# 12V_9V_Power_Stage.net
KiCad netlist of a schematic drawn in Altium Designer
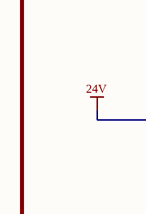
[diagram p0: 12V_9V_Power_Stage.SchDoc, left]
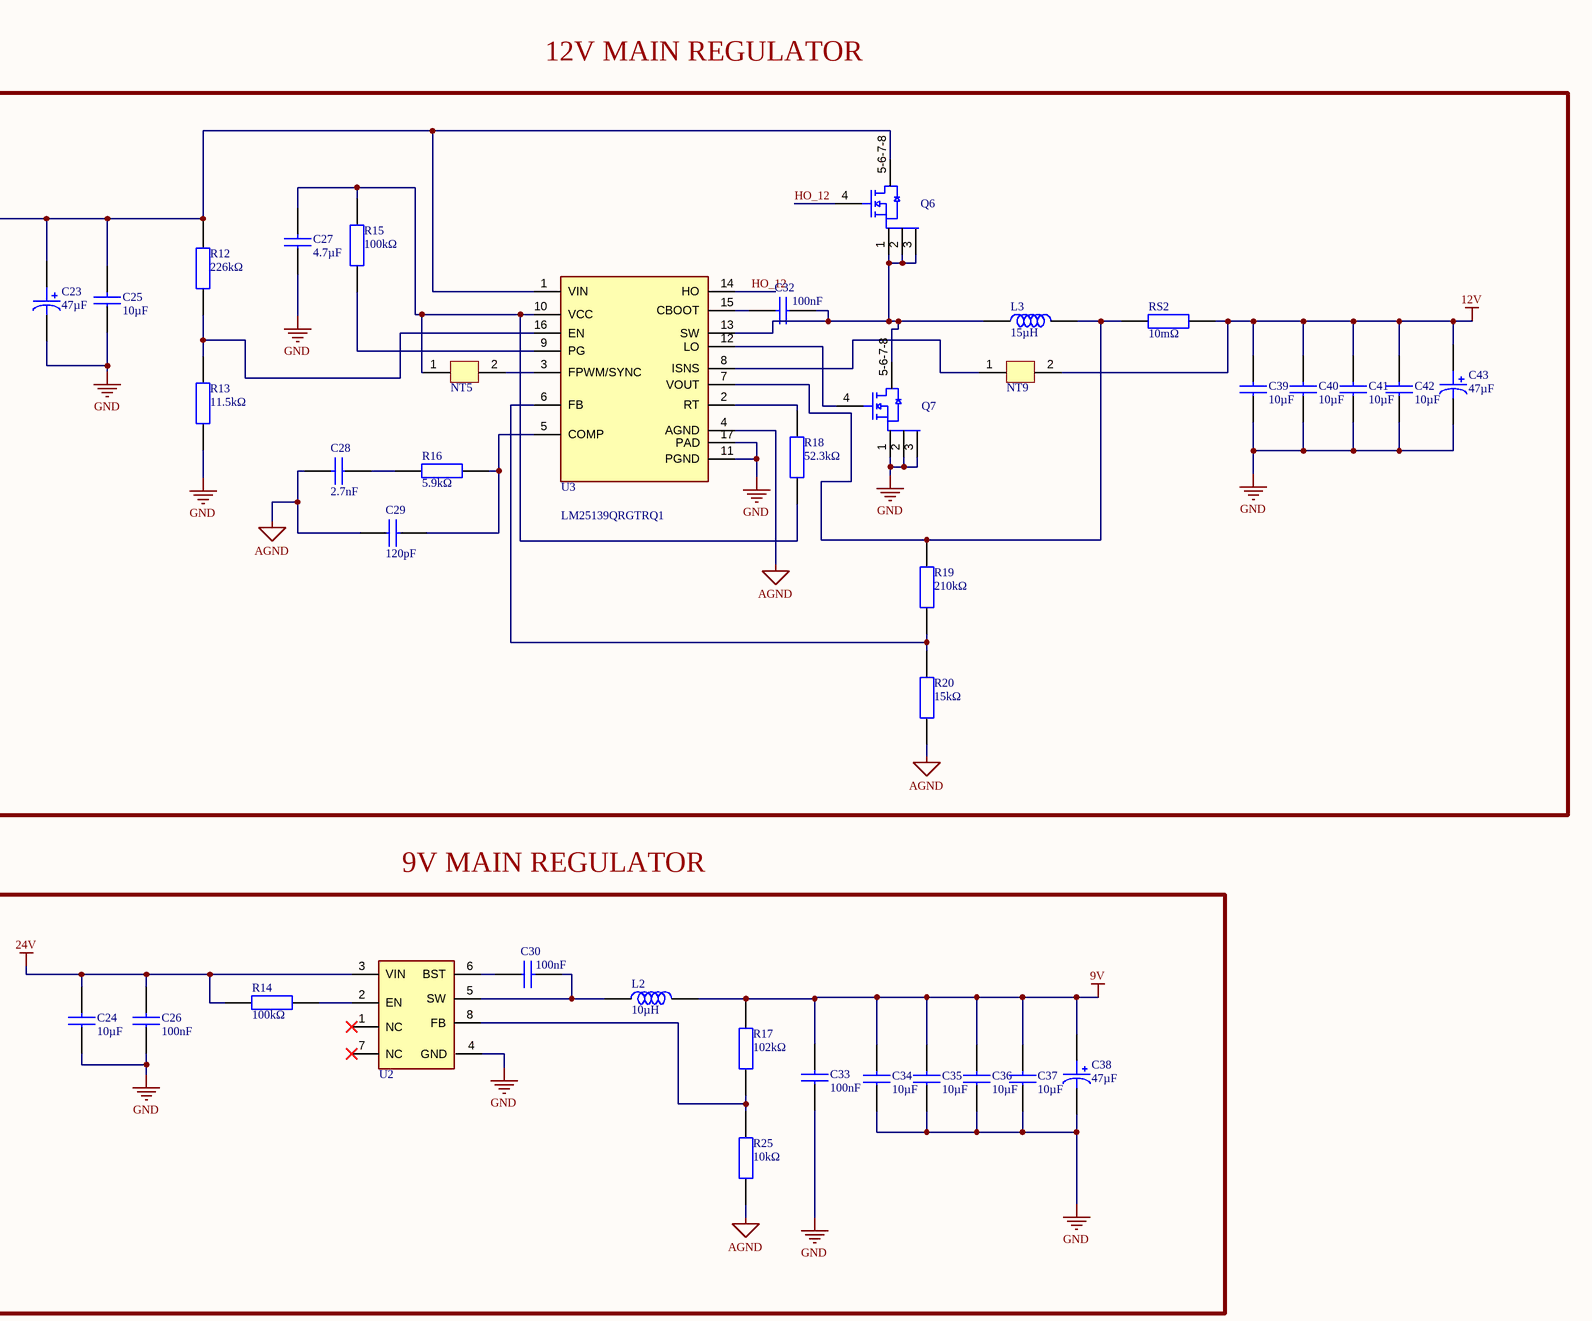
[diagram p1: 12V_9V_Power_Stage.SchDoc, right]

(export (version "E")
  (design (tool "Eeschema 10.0.6"))
  (components
    (comp (ref "C23")
      (value "47µF")
      (footprint "CAP ALUM SMD")
      (description "Conductive Polymer Hybrid Aluminum Electrolytic Capacitors, 47µF, 50V, -55 to 105¡C")
      (fields
        (field (name "MANUFACTURER") "Panasonic")
        (field (name "MANUFACTURER PART NUMBER") "EEH-ZA1H470P")
      )
      (libsource (lib "PDU_BOM") (part "EEHZA1H470P"))
    )
    (comp (ref "C24")
      (value "10µF")
      (footprint "CAP_1210_S")
      (description "50V 10uF X5R 卤10% 1210 Multilayer Ceramic Capacitors MLCC - SMD/SMT ROHS")
      (fields
        (field (name "MANUFACTURER") "Samsung Electro-Mechanics")
        (field (name "MANUFACTURER PART NUMBER") "CL32A106KBJNNNE")
      )
      (libsource (lib "PDU_BOM") (part "CL32A106KBJNNNE"))
    )
    (comp (ref "C25")
      (value "10µF")
      (footprint "CAP_1206")
      (description "50V 10uF X7R 卤10% 1206 Multilayer Ceramic Capacitors MLCC - SMD/SMT ROHS")
      (fields
        (field (name "MANUFACTURER") "TDK")
        (field (name "MANUFACTURER PART NUMBER") "C3216X7R1H106K160AC")
      )
      (libsource (lib "PDU_BOM") (part "C3216X7R1H106K160AC"))
    )
    (comp (ref "C26")
      (value "100nF")
      (footprint "CAP_0603")
      (description "CGA Series 0603 100 nF 50 V ±10 % Tolerance X7R SMT Multilayer Ceramic Capacitor")
      (fields
        (field (name "MANUFACTURER") "TDK")
        (field (name "MANUFACTURER PART NUMBER") "CGA3E2X7R1H104K080AA")
      )
      (libsource (lib "PDU_BOM") (part "CGA3E2X7R1H104K080AA"))
    )
    (comp (ref "C27")
      (value "4.7µF")
      (footprint "CAP_0805")
      (description "10V 4.7uF X7R ±10% 0805 Multilayer Ceramic Capacitors MLCC - SMD/SMT ROHS")
      (fields
        (field (name "MANUFACTURER") "TAIYO YUDEN")
        (field (name "MANUFACTURER PART NUMBER") "LMK212B7475KG-T")
      )
      (libsource (lib "PDU_BOM") (part "LMK212B7475KG-T"))
    )
    (comp (ref "C28")
      (value "2.7nF")
      (footprint "CAP_0603")
      (description "0603 2.7 nF 50 V ±5% Tolerance C0G SMT Multilayer Ceramic Capacitor")
      (fields
        (field (name "MANUFACTURER") "Murata")
        (field (name "MANUFACTURER PART NUMBER") "GRM1885C1H272JA01J")
      )
      (libsource (lib "PDU_BOM") (part "GRM1885C1H272JA01J"))
    )
    (comp (ref "C29")
      (value "120pF")
      (footprint "CAP_0402")
      (description "Multilayer Ceramic Capacitors 120pF 50V C0G 5% SMD 0402")
      (fields
        (field (name "MANUFACTURER") "TAIYO YUDEN")
        (field (name "MANUFACTURER PART NUMBER") "UMK105CG121JV-F")
      )
      (libsource (lib "PDU_BOM") (part "UMK105CG121JV-F"))
    )
    (comp (ref "C30")
      (value "100nF")
      (footprint "CAP_0402")
      (description "C Series 0201 0.1 uF 10 V ±10 % Tolerance X5R SMT Multilayer Ceramic Capacitor")
      (fields
        (field (name "MANUFACTURER") "TDK")
        (field (name "MANUFACTURER PART NUMBER") "C0603X5R1A104K030BC")
      )
      (libsource (lib "PDU_BOM") (part "C0603X5R1A104K030BC"))
    )
    (comp (ref "C32")
      (value "100nF")
      (footprint "CAP_0402")
      (description "10V 100nF X7R ±10% 0402 Multilayer Ceramic Capacitors MLCC - SMD/SMT ROHS")
      (fields
        (field (name "MANUFACTURER") "Murata")
        (field (name "MANUFACTURER PART NUMBER") "GRM155R71A104KA01D")
      )
      (libsource (lib "PDU_BOM") (part "GRM155R71A104KA01D"))
    )
    (comp (ref "C33")
      (value "100nF")
      (footprint "CAP_0603")
      (description "CGA Series 0603 100 nF 50 V ±10 % Tolerance X7R SMT Multilayer Ceramic Capacitor")
      (fields
        (field (name "MANUFACTURER") "TDK")
        (field (name "MANUFACTURER PART NUMBER") "CGA3E2X7R1H104K080AA")
      )
      (libsource (lib "PDU_BOM") (part "CGA3E2X7R1H104K080AA"))
    )
    (comp (ref "C34")
      (value "10µF")
      (footprint "CAP_1206")
      (description "25V 10uF X7R ±10% 1206 Multilayer Ceramic Capacitors MLCC - SMD/SMT ROHS")
      (fields
        (field (name "MANUFACTURER") "Murata")
        (field (name "MANUFACTURER PART NUMBER") "GRM31CR71E106KA12L")
      )
      (libsource (lib "PDU_BOM") (part "GRM31CR71E106KA12L"))
    )
    (comp (ref "C35")
      (value "10µF")
      (footprint "CAP_1206")
      (description "25V 10uF X7R ±10% 1206 Multilayer Ceramic Capacitors MLCC - SMD/SMT ROHS")
      (fields
        (field (name "MANUFACTURER") "Murata")
        (field (name "MANUFACTURER PART NUMBER") "GRM31CR71E106KA12L")
      )
      (libsource (lib "PDU_BOM") (part "GRM31CR71E106KA12L"))
    )
    (comp (ref "C36")
      (value "10µF")
      (footprint "CAP_1206")
      (description "25V 10uF X7R ±10% 1206 Multilayer Ceramic Capacitors MLCC - SMD/SMT ROHS")
      (fields
        (field (name "MANUFACTURER") "Murata")
        (field (name "MANUFACTURER PART NUMBER") "GRM31CR71E106KA12L")
      )
      (libsource (lib "PDU_BOM") (part "GRM31CR71E106KA12L"))
    )
    (comp (ref "C37")
      (value "10µF")
      (footprint "CAP_1206")
      (description "25V 10uF X7R ±10% 1206 Multilayer Ceramic Capacitors MLCC - SMD/SMT ROHS")
      (fields
        (field (name "MANUFACTURER") "Murata")
        (field (name "MANUFACTURER PART NUMBER") "GRM31CR71E106KA12L")
      )
      (libsource (lib "PDU_BOM") (part "GRM31CR71E106KA12L"))
    )
    (comp (ref "C38")
      (value "47µF")
      (footprint "CAP ALUM SMD")
      (description "Conductive Polymer Hybrid Aluminum Electrolytic Capacitors, 47µF, 50V, -55 to 105¡C")
      (fields
        (field (name "MANUFACTURER") "Panasonic")
        (field (name "MANUFACTURER PART NUMBER") "EEH-ZA1H470P")
      )
      (libsource (lib "PDU_BOM") (part "EEHZA1H470P"))
    )
    (comp (ref "C39")
      (value "10µF")
      (footprint "CAP_1206")
      (description "25V 10uF X7R ±10% 1206 Multilayer Ceramic Capacitors MLCC - SMD/SMT ROHS")
      (fields
        (field (name "MANUFACTURER") "Murata")
        (field (name "MANUFACTURER PART NUMBER") "GRM31CR71E106KA12L")
      )
      (libsource (lib "PDU_BOM") (part "GRM31CR71E106KA12L"))
    )
    (comp (ref "C40")
      (value "10µF")
      (footprint "CAP_1206")
      (description "25V 10uF X7R ±10% 1206 Multilayer Ceramic Capacitors MLCC - SMD/SMT ROHS")
      (fields
        (field (name "MANUFACTURER") "Murata")
        (field (name "MANUFACTURER PART NUMBER") "GRM31CR71E106KA12L")
      )
      (libsource (lib "PDU_BOM") (part "GRM31CR71E106KA12L"))
    )
    (comp (ref "C41")
      (value "10µF")
      (footprint "CAP_1206")
      (description "25V 10uF X7R ±10% 1206 Multilayer Ceramic Capacitors MLCC - SMD/SMT ROHS")
      (fields
        (field (name "MANUFACTURER") "Murata")
        (field (name "MANUFACTURER PART NUMBER") "GRM31CR71E106KA12L")
      )
      (libsource (lib "PDU_BOM") (part "GRM31CR71E106KA12L"))
    )
    (comp (ref "C42")
      (value "10µF")
      (footprint "CAP_1206")
      (description "25V 10uF X7R ±10% 1206 Multilayer Ceramic Capacitors MLCC - SMD/SMT ROHS")
      (fields
        (field (name "MANUFACTURER") "Murata")
        (field (name "MANUFACTURER PART NUMBER") "GRM31CR71E106KA12L")
      )
      (libsource (lib "PDU_BOM") (part "GRM31CR71E106KA12L"))
    )
    (comp (ref "C43")
      (value "47µF")
      (footprint "CAP ALUM SMD")
      (description "Conductive Polymer Hybrid Aluminum Electrolytic Capacitors, 47µF, 50V, -55 to 105¡C")
      (fields
        (field (name "MANUFACTURER") "Panasonic")
        (field (name "MANUFACTURER PART NUMBER") "EEH-ZA1H470P")
      )
      (libsource (lib "PDU_BOM") (part "EEHZA1H470P"))
    )
    (comp (ref "L2")
      (value "10µH")
      (footprint "SRR1208")
      (description "Inductor Power Shielded Wirewound 10uH 20% 1KHz 20Q-Factor Ferrite 5A 0.021Ohm DCR T/R")
      (fields
        (field (name "MANUFACTURER") "Bourns")
        (field (name "MANUFACTURER PART NUMBER") "SRR1208-100ML")
      )
      (libsource (lib "PDU_BOM") (part "SRR1208-100ML"))
    )
    (comp (ref "L3")
      (value "15µH")
      (footprint "MSS1210")
      (description "General Purpose Inductor, 15uH, 20%, 1 Element, Ferrite-Core, SMD, 4848, CHIP, 4747")
      (fields
        (field (name "MANUFACTURER") "Coilcraft")
        (field (name "MANUFACTURER PART NUMBER") "MSS1210-153MED")
      )
      (libsource (lib "PDU_BOM") (part "MSS1210-153MED"))
    )
    (comp (ref "NT5") (value "Net-Tie") (footprint "Net-Tie") (libsource (lib "PDU_BOM") (part "Net-Tie")))
    (comp (ref "NT9") (value "Net-Tie") (footprint "Net-Tie") (libsource (lib "PDU_BOM") (part "Net-Tie")))
    (comp (ref "Q6")
      (value "CSD18540Q5B")
      (footprint "SON 5X6")
      (description "60-V, N channel NexFET™ power MOSFET, single SON 5 mm x 6 mm, 2.2 mOhm 8-VSON-CLIP -55 to 175")
      (fields (field (name "MANUFACTURER") "Texas Instruments"))
      (libsource (lib "PDU_BOM") (part "CSD18540Q5B"))
    )
    (comp (ref "Q7")
      (value "CSD18540Q5B")
      (footprint "SON 5X6")
      (description "60-V, N channel NexFET™ power MOSFET, single SON 5 mm x 6 mm, 2.2 mOhm 8-VSON-CLIP -55 to 175")
      (fields (field (name "MANUFACTURER") "Texas Instruments"))
      (libsource (lib "PDU_BOM") (part "CSD18540Q5B"))
    )
    (comp (ref "R12")
      (value "226kΩ")
      (footprint "RES_0402")
      (description "Fixed Resistor, Metal Glaze/Thick Film, 0.063W, 226000ohm, 50V, 1% +/-Tol, Surface Mount, 0402")
      (fields
        (field (name "MANUFACTURER") "Vishay")
        (field (name "MANUFACTURER PART NUMBER") "CRCW0402226KFKED")
      )
      (libsource (lib "PDU_BOM") (part "CRCW0402226KFKED"))
    )
    (comp (ref "R13")
      (value "11.5kΩ")
      (footprint "RES_0402")
      (description "Res Thick Film 0402 11.5K Ohm 1% 1/16W ±100ppm/°C Molded SMD SMD Paper T/R")
      (fields
        (field (name "MANUFACTURER") "Vishay")
        (field (name "MANUFACTURER PART NUMBER") "CRCW040211K5FKED")
      )
      (libsource (lib "PDU_BOM") (part "CRCW040211K5FKED"))
    )
    (comp (ref "R14")
      (value "100kΩ")
      (footprint "RES_0603")
      (description "Res Thick Film 0603 100K Ohm 1% 1/3W ±100ppm/°C Molded SMD SMD Paper T/R")
      (fields
        (field (name "MANUFACTURER") "Vishay")
        (field (name "MANUFACTURER PART NUMBER") "CRCW0603100KFKEAHP")
      )
      (libsource (lib "") (part "CRCW0603100KFKEA_1"))
    )
    (comp (ref "R15")
      (value "100kΩ")
      (footprint "RES_0603")
      (description "Res Thick Film 0603 100K Ohm 1% 1/3W ±100ppm/°C Molded SMD SMD Paper T/R")
      (fields
        (field (name "MANUFACTURER") "Vishay")
        (field (name "MANUFACTURER PART NUMBER") "CRCW0603100KFKEAHP")
      )
      (libsource (lib "PDU_BOM") (part "CRCW0603100KFKEA"))
    )
    (comp (ref "R16")
      (value "5.9kΩ")
      (footprint "RES_0402")
      (description "Res Thick Film 0402 5.9K Ohm 1% 1/16W ±100ppm/°C Molded SMD Paper T/R")
      (fields
        (field (name "MANUFACTURER") "Vishay")
        (field (name "MANUFACTURER PART NUMBER") "CRCW04025K90FKED")
      )
      (libsource (lib "PDU_BOM") (part "CRCW04025K90FKED"))
    )
    (comp (ref "R17")
      (value "102kΩ")
      (footprint "RES_0402")
      (description "63mW Thick Film Resistors 75V ±1% ±100ppm/℃ 102kΩ 0402 Chip Resistor - Surface Mount ROHS")
      (fields
        (field (name "MANUFACTURER") "Vishay")
        (field (name "MANUFACTURER PART NUMBER") "CRCW0402102KFKED")
      )
      (libsource (lib "PDU_BOM") (part "CRCW0402102KFKED"))
    )
    (comp (ref "R18")
      (value "52.3kΩ")
      (footprint "RES_0603")
      (description "100mW Thick Film Resistors 75V ±1% ±100ppm/℃ 52.3kΩ 0603 Chip Resistor - Surface Mount ROHS")
      (fields
        (field (name "MANUFACTURER") "Vishay")
        (field (name "MANUFACTURER PART NUMBER") "CRCW060352K3FKEA")
      )
      (libsource (lib "PDU_BOM") (part "CRCW060352K3FKEA"))
    )
    (comp (ref "R19")
      (value "210kΩ")
      (footprint "RES_0402")
      (description "62.5mW Thick Film Resistors 50V ±1% ±100ppm/℃ 210kΩ 0402 Chip Resistor - Surface Mount ROHS")
      (fields
        (field (name "MANUFACTURER") "Vishay")
        (field (name "MANUFACTURER PART NUMBER") "CRCW0402210KFKED")
      )
      (libsource (lib "PDU_BOM") (part "CRCW0402210KFKED"))
    )
    (comp (ref "R20")
      (value "15kΩ")
      (footprint "RES_0402")
      (description "Res Thick Film 0402 15K Ohm 1% 1/16W ±100ppm/°C Molded SMD Paper T/R")
      (fields
        (field (name "MANUFACTURER") "Vishay")
        (field (name "MANUFACTURER PART NUMBER") "CRCW040215K0FKED")
      )
      (libsource (lib "PDU_BOM") (part "CRCW040215K0FKED"))
    )
    (comp (ref "R25")
      (value "10kΩ")
      (footprint "RES_0402")
      (description "Res Thick Film 0402 10K Ohm 1% 0.2W ±100ppm/°C Molded SMD SMD Paper T/R")
      (fields
        (field (name "MANUFACTURER") "Vishay")
        (field (name "MANUFACTURER PART NUMBER") "CRCW040210K0FKEDHP")
      )
      (libsource (lib "PDU_BOM") (part "CRCW040210K0FKED"))
    )
    (comp (ref "RS2")
      (value "10mΩ")
      (footprint "CAP_1206")
      (description "Res Thick Film 1206 0.01 Ohm 1% 1/2W Molded SMD Paper T/R")
      (fields
        (field (name "MANUFACTURER") "Stackpole Electronics")
        (field (name "MANUFACTURER PART NUMBER") "CSR1206FK10L0")
      )
      (libsource (lib "PDU_BOM") (part "CSR1206FK10L0"))
    )
    (comp (ref "U2")
      (value "TPS563300DRLR")
      (footprint "SOT-583-8")
      (description "3.8-V to 28-V Input, 3-A synchronous buck converter in SOT-583 package 8-SOT-5X3 -40 to 150")
      (fields (field (name "MANUFACTURER") "Texas Instruments"))
      (libsource (lib "PDU_BOM") (part "TPS563300DRLR"))
    )
    (comp (ref "U3")
      (value "LM25139QRGTRQ1")
      (footprint "16-VFQFN")
      (fields (field (name "MANUFACTURER") "Texas Instruments"))
      (libsource (lib "PDU_BOM") (part "LM25139QRGTRQ1"))
    )
  )
  (nets
    (net (code "1") (name "/HO_12") (class "Default")
      (node (ref "Q6") (pin "4") (pinfunction "G_4") (pintype "passive"))
      (node (ref "U3") (pin "14") (pinfunction "HO_14") (pintype "passive"))
    )
    (net (code "2") (name "9V") (class "Default")
      (node (ref "C33") (pin "2") (pinfunction "2_2") (pintype "passive"))
      (node (ref "C34") (pin "2") (pinfunction "2_2") (pintype "passive"))
      (node (ref "C35") (pin "2") (pinfunction "2_2") (pintype "passive"))
      (node (ref "C36") (pin "2") (pinfunction "2_2") (pintype "passive"))
      (node (ref "C37") (pin "2") (pinfunction "2_2") (pintype "passive"))
      (node (ref "C38") (pin "1") (pinfunction "C_1") (pintype "passive"))
      (node (ref "L2") (pin "2") (pinfunction "2_2") (pintype "passive"))
      (node (ref "R17") (pin "2") (pinfunction "2_2") (pintype "passive"))
    )
    (net (code "3") (name "12V") (class "Default")
      (node (ref "C39") (pin "2") (pinfunction "2_2") (pintype "passive"))
      (node (ref "C40") (pin "2") (pinfunction "2_2") (pintype "passive"))
      (node (ref "C41") (pin "2") (pinfunction "2_2") (pintype "passive"))
      (node (ref "C42") (pin "2") (pinfunction "2_2") (pintype "passive"))
      (node (ref "C43") (pin "1") (pinfunction "C_1") (pintype "passive"))
      (node (ref "NT9") (pin "2") (pinfunction "2_2") (pintype "passive"))
      (node (ref "RS2") (pin "2") (pinfunction "2_2") (pintype "passive"))
    )
    (net (code "4") (name "24V") (class "Default")
      (node (ref "C23") (pin "1") (pinfunction "C_1") (pintype "passive"))
      (node (ref "C24") (pin "2") (pinfunction "2_2") (pintype "passive"))
      (node (ref "C25") (pin "2") (pinfunction "2_2") (pintype "passive"))
      (node (ref "C26") (pin "2") (pinfunction "2_2") (pintype "passive"))
      (node (ref "Q6") (pin "5-6-7-8") (pinfunction "D_5-6-7-8") (pintype "passive"))
      (node (ref "R12") (pin "2") (pinfunction "2_2") (pintype "passive"))
      (node (ref "R14") (pin "1") (pinfunction "1_1") (pintype "passive"))
      (node (ref "U2") (pin "3") (pinfunction "VIN_3") (pintype "passive"))
      (node (ref "U3") (pin "1") (pinfunction "VIN_1") (pintype "passive"))
    )
    (net (code "5") (name "AGND") (class "Default")
      (node (ref "C28") (pin "2") (pinfunction "2_2") (pintype "passive"))
      (node (ref "C29") (pin "1") (pinfunction "1_1") (pintype "passive"))
      (node (ref "R20") (pin "1") (pinfunction "1_1") (pintype "passive"))
      (node (ref "R25") (pin "1") (pinfunction "1_1") (pintype "passive"))
      (node (ref "U3") (pin "4") (pinfunction "AGND_4") (pintype "passive"))
    )
    (net (code "6") (name "GND") (class "Default")
      (node (ref "C23") (pin "2") (pinfunction "A_2") (pintype "passive"))
      (node (ref "C24") (pin "1") (pinfunction "1_1") (pintype "passive"))
      (node (ref "C25") (pin "1") (pinfunction "1_1") (pintype "passive"))
      (node (ref "C26") (pin "1") (pinfunction "1_1") (pintype "passive"))
      (node (ref "C27") (pin "1") (pinfunction "1_1") (pintype "passive"))
      (node (ref "C33") (pin "1") (pinfunction "1_1") (pintype "passive"))
      (node (ref "C34") (pin "1") (pinfunction "1_1") (pintype "passive"))
      (node (ref "C35") (pin "1") (pinfunction "1_1") (pintype "passive"))
      (node (ref "C36") (pin "1") (pinfunction "1_1") (pintype "passive"))
      (node (ref "C37") (pin "1") (pinfunction "1_1") (pintype "passive"))
      (node (ref "C38") (pin "2") (pinfunction "A_2") (pintype "passive"))
      (node (ref "C39") (pin "1") (pinfunction "1_1") (pintype "passive"))
      (node (ref "C40") (pin "1") (pinfunction "1_1") (pintype "passive"))
      (node (ref "C41") (pin "1") (pinfunction "1_1") (pintype "passive"))
      (node (ref "C42") (pin "1") (pinfunction "1_1") (pintype "passive"))
      (node (ref "C43") (pin "2") (pinfunction "A_2") (pintype "passive"))
      (node (ref "Q7") (pin "1") (pinfunction "S_1") (pintype "passive"))
      (node (ref "Q7") (pin "2") (pinfunction "S_2") (pintype "passive"))
      (node (ref "Q7") (pin "3") (pinfunction "S_3") (pintype "passive"))
      (node (ref "R13") (pin "1") (pinfunction "1_1") (pintype "passive"))
      (node (ref "U2") (pin "4") (pinfunction "GND_4") (pintype "passive"))
      (node (ref "U3") (pin "11") (pinfunction "PGND_11") (pintype "passive"))
      (node (ref "U3") (pin "17") (pinfunction "PAD_17") (pintype "passive"))
    )
    (net (code "7") (name "Net-(C28-Pad1)") (class "Default")
      (node (ref "C28") (pin "1") (pinfunction "1_1") (pintype "passive"))
      (node (ref "R16") (pin "1") (pinfunction "1_1") (pintype "passive"))
    )
    (net (code "8") (name "Net-(Q7-D)") (class "Default")
      (node (ref "C32") (pin "1") (pinfunction "1_1") (pintype "passive"))
      (node (ref "L3") (pin "1") (pinfunction "1_1") (pintype "passive"))
      (node (ref "Q6") (pin "1") (pinfunction "S_1") (pintype "passive"))
      (node (ref "Q6") (pin "2") (pinfunction "S_2") (pintype "passive"))
      (node (ref "Q6") (pin "3") (pinfunction "S_3") (pintype "passive"))
      (node (ref "Q7") (pin "5-6-7-8") (pinfunction "D_5-6-7-8") (pintype "passive"))
      (node (ref "U3") (pin "13") (pinfunction "SW_13") (pintype "passive"))
    )
    (net (code "9") (name "Net-(Q7-G)") (class "Default")
      (node (ref "Q7") (pin "4") (pinfunction "G_4") (pintype "passive"))
      (node (ref "U3") (pin "12") (pinfunction "LO_12") (pintype "passive"))
    )
    (net (code "10") (name "Net-(U2-BST)") (class "Default")
      (node (ref "C30") (pin "1") (pinfunction "1_1") (pintype "passive"))
      (node (ref "U2") (pin "6") (pinfunction "BST_6") (pintype "passive"))
    )
    (net (code "11") (name "Net-(U2-EN)") (class "Default")
      (node (ref "R14") (pin "2") (pinfunction "2_2") (pintype "passive"))
      (node (ref "U2") (pin "2") (pinfunction "EN_2") (pintype "passive"))
    )
    (net (code "12") (name "Net-(U2-FB)") (class "Default")
      (node (ref "R17") (pin "1") (pinfunction "1_1") (pintype "passive"))
      (node (ref "R25") (pin "2") (pinfunction "2_2") (pintype "passive"))
      (node (ref "U2") (pin "8") (pinfunction "FB_8") (pintype "passive"))
    )
    (net (code "13") (name "Net-(U2-SW)") (class "Default")
      (node (ref "C30") (pin "2") (pinfunction "2_2") (pintype "passive"))
      (node (ref "L2") (pin "1") (pinfunction "1_1") (pintype "passive"))
      (node (ref "U2") (pin "5") (pinfunction "SW_5") (pintype "passive"))
    )
    (net (code "14") (name "Net-(U3-CBOOT)") (class "Default")
      (node (ref "C32") (pin "2") (pinfunction "2_2") (pintype "passive"))
      (node (ref "U3") (pin "15") (pinfunction "CBOOT_15") (pintype "passive"))
    )
    (net (code "15") (name "Net-(U3-COMP)") (class "Default")
      (node (ref "C29") (pin "2") (pinfunction "2_2") (pintype "passive"))
      (node (ref "R16") (pin "2") (pinfunction "2_2") (pintype "passive"))
      (node (ref "U3") (pin "5") (pinfunction "COMP_5") (pintype "passive"))
    )
    (net (code "16") (name "Net-(U3-EN)") (class "Default")
      (node (ref "R12") (pin "1") (pinfunction "1_1") (pintype "passive"))
      (node (ref "R13") (pin "2") (pinfunction "2_2") (pintype "passive"))
      (node (ref "U3") (pin "16") (pinfunction "EN_16") (pintype "passive"))
    )
    (net (code "17") (name "Net-(U3-FB)") (class "Default")
      (node (ref "R19") (pin "1") (pinfunction "1_1") (pintype "passive"))
      (node (ref "R20") (pin "2") (pinfunction "2_2") (pintype "passive"))
      (node (ref "U3") (pin "6") (pinfunction "FB_6") (pintype "passive"))
    )
    (net (code "18") (name "Net-(U3-FPWM{slash}SYNC)") (class "Default")
      (node (ref "NT5") (pin "2") (pinfunction "2_2") (pintype "passive"))
      (node (ref "U3") (pin "3") (pinfunction "FPWM/SYNC_3") (pintype "passive"))
    )
    (net (code "19") (name "Net-(U3-ISNS)") (class "Default")
      (node (ref "NT9") (pin "1") (pinfunction "1_1") (pintype "passive"))
      (node (ref "U3") (pin "8") (pinfunction "ISNS_8") (pintype "passive"))
    )
    (net (code "20") (name "Net-(U3-PG)") (class "Default")
      (node (ref "R15") (pin "1") (pinfunction "1_1") (pintype "passive"))
      (node (ref "U3") (pin "9") (pinfunction "PG_9") (pintype "passive"))
    )
    (net (code "21") (name "Net-(U3-RT)") (class "Default")
      (node (ref "R18") (pin "2") (pinfunction "2_2") (pintype "passive"))
      (node (ref "U3") (pin "2") (pinfunction "RT_2") (pintype "passive"))
    )
    (net (code "22") (name "Net-(U3-VCC)") (class "Default")
      (node (ref "C27") (pin "2") (pinfunction "2_2") (pintype "passive"))
      (node (ref "NT5") (pin "1") (pinfunction "1_1") (pintype "passive"))
      (node (ref "R15") (pin "2") (pinfunction "2_2") (pintype "passive"))
      (node (ref "R18") (pin "1") (pinfunction "1_1") (pintype "passive"))
      (node (ref "U3") (pin "10") (pinfunction "VCC_10") (pintype "passive"))
    )
    (net (code "23") (name "Net-(U3-VOUT)") (class "Default")
      (node (ref "L3") (pin "2") (pinfunction "2_2") (pintype "passive"))
      (node (ref "R19") (pin "2") (pinfunction "2_2") (pintype "passive"))
      (node (ref "RS2") (pin "1") (pinfunction "1_1") (pintype "passive"))
      (node (ref "U3") (pin "7") (pinfunction "VOUT_7") (pintype "passive"))
    )
    (net (code "24") (name "unconnected-(U2-NC-Pad1)") (class "Default")
      (node (ref "U2") (pin "1") (pinfunction "NC_1") (pintype "passive+no_connect"))
    )
    (net (code "25") (name "unconnected-(U2-NC-Pad7)") (class "Default")
      (node (ref "U2") (pin "7") (pinfunction "NC_7") (pintype "passive+no_connect"))
    )
  )
)
